# MSP430.net
KiCad netlist of a schematic drawn in Altium Designer
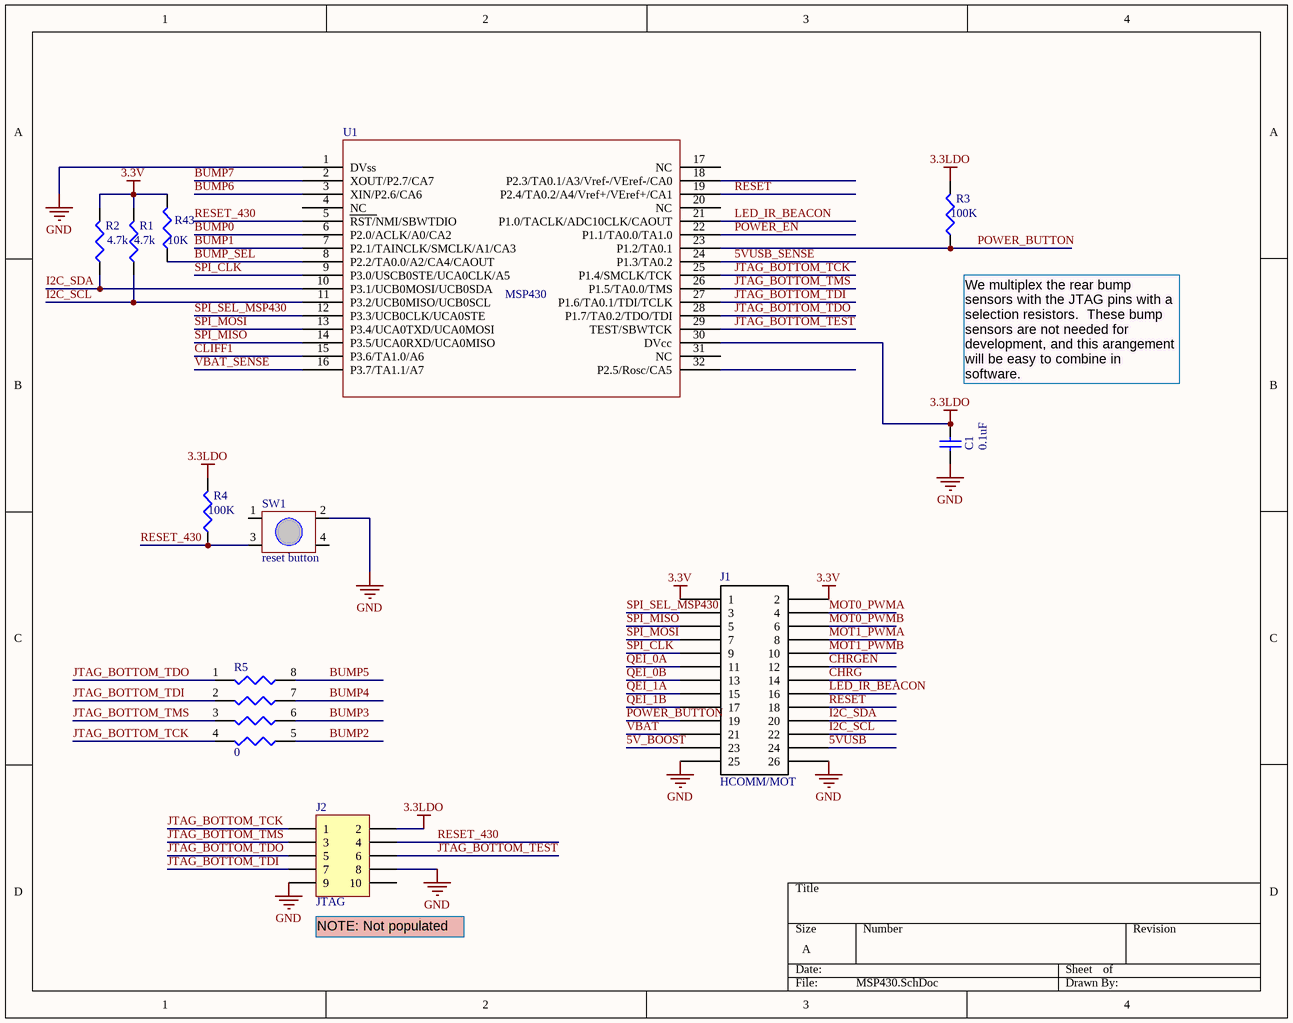
[diagram p0: MSP430.SchDoc]

(export (version "E")
  (design (tool "Eeschema 10.0.6"))
  (components
    (comp (ref "C1")
      (value "0.1uF")
      (footprint "CAPC1005L")
      (description "Capacitor (Semiconductor SIM Model)")
      (fields (field (name "Comment") "Cap Semi") (field (name "PUBLISHER") "Altium Limited"))
      (libsource (lib "Miscellaneous Devices") (part "Cap Semi"))
    )
    (comp (ref "J1")
      (value "HCOMM/MOT")
      (footprint "HeaderSM 13x2")
      (description "Header, 2X20, 50mil, IDC")
      (libsource (lib "mrone") (part "HCOMM/HMOT"))
    )
    (comp (ref "J2")
      (value "JTAG")
      (footprint "HDR2X5")
      (description "Header, 5-Pin, Dual row")
      (fields (field (name "PUBLISHER") "Altium Limited"))
      (libsource (lib "Miscellaneous Connectors") (part "Header 5X2"))
    )
    (comp (ref "R1")
      (value "4.7k")
      (footprint "RESC1608L")
      (description "Resistor")
      (fields (field (name "Comment") "Res3") (field (name "PUBLISHER") "Altium Limited"))
      (libsource (lib "Miscellaneous Devices") (part "Res3"))
    )
    (comp (ref "R2")
      (value "4.7k")
      (footprint "RESC1608L")
      (description "Resistor")
      (fields (field (name "Comment") "Res3") (field (name "PUBLISHER") "Altium Limited"))
      (libsource (lib "Miscellaneous Devices") (part "Res3"))
    )
    (comp (ref "R3")
      (value "100K")
      (footprint "RESC1608L")
      (description "Resistor")
      (fields (field (name "Comment") "Res3") (field (name "PUBLISHER") "Altium Limited"))
      (libsource (lib "Miscellaneous Devices") (part "Res3"))
    )
    (comp (ref "R4")
      (value "100K")
      (footprint "RESC1608L")
      (description "Resistor")
      (fields (field (name "Comment") "Res3") (field (name "PUBLISHER") "Altium Limited"))
      (libsource (lib "Miscellaneous Devices") (part "Res3"))
    )
    (comp (ref "R5") (value "0") (footprint "4-RES ARRAY") (libsource (lib "mrone") (part "4 Res Array")))
    (comp (ref "R43")
      (value "10K")
      (footprint "RESC1608L")
      (description "Resistor")
      (fields (field (name "Comment") "Res3") (field (name "PUBLISHER") "Altium Limited"))
      (libsource (lib "Miscellaneous Devices") (part "Res3"))
    )
    (comp (ref "SW1")
      (value "reset button")
      (footprint "SwitchTall-TL330")
      (libsource (lib "mrone") (part "Switch-TL330"))
    )
    (comp (ref "U1")
      (value "MSP430")
      (footprint "MSP430_32PIN")
      (libsource (lib "mrone") (part "MSP430_32pin"))
    )
  )
  (nets
    (net (code "1") (name "/5VUSB") (class "Default")
      (node (ref "J1") (pin "24") (pinfunction "24_24") (pintype "passive"))
    )
    (net (code "2") (name "/5VUSB_SENSE") (class "Default")
      (node (ref "U1") (pin "24") (pinfunction "P1.3/TA0.2_24") (pintype "passive"))
    )
    (net (code "3") (name "/5V_BOOST") (class "Default")
      (node (ref "J1") (pin "23") (pinfunction "23_23") (pintype "passive"))
    )
    (net (code "4") (name "/BUMP0") (class "Default")
      (node (ref "U1") (pin "6") (pinfunction "P2.0/ACLK/A0/CA2_6") (pintype "passive"))
    )
    (net (code "5") (name "/BUMP1") (class "Default")
      (node (ref "U1") (pin "7") (pinfunction "P2.1/TAINCLK/SMCLK/A1/CA3_7") (pintype "passive"))
    )
    (net (code "6") (name "/BUMP2") (class "Default")
      (node (ref "R5") (pin "5") (pinfunction "5_5") (pintype "passive"))
    )
    (net (code "7") (name "/BUMP3") (class "Default")
      (node (ref "R5") (pin "6") (pinfunction "6_6") (pintype "passive"))
    )
    (net (code "8") (name "/BUMP4") (class "Default")
      (node (ref "R5") (pin "7") (pinfunction "7_7") (pintype "passive"))
    )
    (net (code "9") (name "/BUMP5") (class "Default")
      (node (ref "R5") (pin "8") (pinfunction "8_8") (pintype "passive"))
    )
    (net (code "10") (name "/BUMP6") (class "Default")
      (node (ref "U1") (pin "3") (pinfunction "XIN/P2.6/CA6_3") (pintype "passive"))
    )
    (net (code "11") (name "/BUMP7") (class "Default")
      (node (ref "U1") (pin "2") (pinfunction "XOUT/P2.7/CA7_2") (pintype "passive"))
    )
    (net (code "12") (name "/BUMP_SEL") (class "Default")
      (node (ref "R43") (pin "1") (pinfunction "1_1") (pintype "passive"))
      (node (ref "U1") (pin "8") (pinfunction "P2.2/TA0.0/A2/CA4/CAOUT_8") (pintype "passive"))
    )
    (net (code "13") (name "/CHRG") (class "Default")
      (node (ref "J1") (pin "14") (pinfunction "14_14") (pintype "passive"))
    )
    (net (code "14") (name "/CHRGEN") (class "Default")
      (node (ref "J1") (pin "12") (pinfunction "12_12") (pintype "passive"))
    )
    (net (code "15") (name "/CLIFF1") (class "Default")
      (node (ref "U1") (pin "15") (pinfunction "P3.6/TA1.0/A6_15") (pintype "passive"))
    )
    (net (code "16") (name "/I2C_SCL") (class "Default")
      (node (ref "J1") (pin "22") (pinfunction "22_22") (pintype "passive"))
      (node (ref "R1") (pin "1") (pinfunction "1_1") (pintype "passive"))
      (node (ref "U1") (pin "11") (pinfunction "P3.2/UCB0MISO/UCB0SCL_11") (pintype "passive"))
    )
    (net (code "17") (name "/I2C_SDA") (class "Default")
      (node (ref "J1") (pin "20") (pinfunction "20_20") (pintype "passive"))
      (node (ref "R2") (pin "1") (pinfunction "1_1") (pintype "passive"))
      (node (ref "U1") (pin "10") (pinfunction "P3.1/UCB0MOSI/UCB0SDA_10") (pintype "passive"))
    )
    (net (code "18") (name "/JTAG_BOTTOM_TCK") (class "Default")
      (node (ref "J2") (pin "1") (pinfunction "1_1") (pintype "passive"))
      (node (ref "R5") (pin "4") (pinfunction "4_4") (pintype "passive"))
      (node (ref "U1") (pin "25") (pinfunction "P1.4/SMCLK/TCK_25") (pintype "passive"))
    )
    (net (code "19") (name "/JTAG_BOTTOM_TDI") (class "Default")
      (node (ref "J2") (pin "7") (pinfunction "7_7") (pintype "passive"))
      (node (ref "R5") (pin "2") (pinfunction "2_2") (pintype "passive"))
      (node (ref "U1") (pin "27") (pinfunction "P1.6/TA0.1/TDI/TCLK_27") (pintype "passive"))
    )
    (net (code "20") (name "/JTAG_BOTTOM_TDO") (class "Default")
      (node (ref "J2") (pin "5") (pinfunction "5_5") (pintype "passive"))
      (node (ref "R5") (pin "1") (pinfunction "1_1") (pintype "passive"))
      (node (ref "U1") (pin "28") (pinfunction "P1.7/TA0.2/TDO/TDI_28") (pintype "passive"))
    )
    (net (code "21") (name "/JTAG_BOTTOM_TEST") (class "Default")
      (node (ref "J2") (pin "6") (pinfunction "6_6") (pintype "passive"))
      (node (ref "U1") (pin "29") (pinfunction "TEST/SBWTCK_29") (pintype "passive"))
    )
    (net (code "22") (name "/JTAG_BOTTOM_TMS") (class "Default")
      (node (ref "J2") (pin "3") (pinfunction "3_3") (pintype "passive"))
      (node (ref "R5") (pin "3") (pinfunction "3_3") (pintype "passive"))
      (node (ref "U1") (pin "26") (pinfunction "P1.5/TA0.0/TMS_26") (pintype "passive"))
    )
    (net (code "23") (name "/LED_IR_BEACON") (class "Default")
      (node (ref "J1") (pin "16") (pinfunction "16_16") (pintype "passive"))
      (node (ref "U1") (pin "21") (pinfunction "P1.0/TACLK/ADC10CLK/CAOUT_21") (pintype "passive"))
    )
    (net (code "24") (name "/MOT0_PWMA") (class "Default")
      (node (ref "J1") (pin "4") (pinfunction "4_4") (pintype "passive"))
    )
    (net (code "25") (name "/MOT0_PWMB") (class "Default")
      (node (ref "J1") (pin "6") (pinfunction "6_6") (pintype "passive"))
    )
    (net (code "26") (name "/MOT1_PWMA") (class "Default")
      (node (ref "J1") (pin "8") (pinfunction "8_8") (pintype "passive"))
    )
    (net (code "27") (name "/MOT1_PWMB") (class "Default")
      (node (ref "J1") (pin "10") (pinfunction "10_10") (pintype "passive"))
    )
    (net (code "28") (name "/POWER_BUTTON") (class "Default")
      (node (ref "J1") (pin "19") (pinfunction "19_19") (pintype "passive"))
      (node (ref "R3") (pin "1") (pinfunction "1_1") (pintype "passive"))
      (node (ref "U1") (pin "23") (pinfunction "P1.2/TA0.1_23") (pintype "passive"))
    )
    (net (code "29") (name "/POWER_EN") (class "Default")
      (node (ref "U1") (pin "22") (pinfunction "P1.1/TA0.0/TA1.0_22") (pintype "passive"))
    )
    (net (code "30") (name "/QEI_0A") (class "Default")
      (node (ref "J1") (pin "11") (pinfunction "11_11") (pintype "passive"))
    )
    (net (code "31") (name "/QEI_0B") (class "Default")
      (node (ref "J1") (pin "13") (pinfunction "13_13") (pintype "passive"))
    )
    (net (code "32") (name "/QEI_1A") (class "Default")
      (node (ref "J1") (pin "15") (pinfunction "15_15") (pintype "passive"))
    )
    (net (code "33") (name "/QEI_1B") (class "Default")
      (node (ref "J1") (pin "17") (pinfunction "17_17") (pintype "passive"))
    )
    (net (code "34") (name "/RESET") (class "Default")
      (node (ref "J1") (pin "18") (pinfunction "18_18") (pintype "passive"))
      (node (ref "U1") (pin "19") (pinfunction "P2.4/TA0.2/A4/Vref+/VEref+/CA1_19") (pintype "passive"))
    )
    (net (code "35") (name "/RESET_430") (class "Default")
      (node (ref "J2") (pin "4") (pinfunction "4_4") (pintype "passive"))
      (node (ref "R4") (pin "1") (pinfunction "1_1") (pintype "passive"))
      (node (ref "SW1") (pin "3") (pinfunction "3_3") (pintype "passive"))
      (node (ref "U1") (pin "5") (pinfunction "RST/NMI/SBWTDIO_5") (pintype "passive"))
    )
    (net (code "36") (name "/SPI_CLK") (class "Default")
      (node (ref "J1") (pin "9") (pinfunction "9_9") (pintype "passive"))
      (node (ref "U1") (pin "9") (pinfunction "P3.0/USCB0STE/UCA0CLK/A5_9") (pintype "passive"))
    )
    (net (code "37") (name "/SPI_MISO") (class "Default")
      (node (ref "J1") (pin "5") (pinfunction "5_5") (pintype "passive"))
      (node (ref "U1") (pin "14") (pinfunction "P3.5/UCA0RXD/UCA0MISO_14") (pintype "passive"))
    )
    (net (code "38") (name "/SPI_MOSI") (class "Default")
      (node (ref "J1") (pin "7") (pinfunction "7_7") (pintype "passive"))
      (node (ref "U1") (pin "13") (pinfunction "P3.4/UCA0TXD/UCA0MOSI_13") (pintype "passive"))
    )
    (net (code "39") (name "/SPI_SEL_MSP430") (class "Default")
      (node (ref "J1") (pin "3") (pinfunction "3_3") (pintype "passive"))
      (node (ref "U1") (pin "12") (pinfunction "P3.3/UCB0CLK/UCA0STE_12") (pintype "passive"))
    )
    (net (code "40") (name "/VBAT") (class "Default")
      (node (ref "J1") (pin "21") (pinfunction "21_21") (pintype "passive"))
    )
    (net (code "41") (name "/VBAT_SENSE") (class "Default")
      (node (ref "U1") (pin "16") (pinfunction "P3.7/TA1.1/A7_16") (pintype "passive"))
    )
    (net (code "42") (name "3.3LDO") (class "Default")
      (node (ref "C1") (pin "2") (pinfunction "2_2") (pintype "passive"))
      (node (ref "J2") (pin "2") (pinfunction "2_2") (pintype "passive"))
      (node (ref "R3") (pin "2") (pinfunction "2_2") (pintype "passive"))
      (node (ref "R4") (pin "2") (pinfunction "2_2") (pintype "passive"))
      (node (ref "U1") (pin "30") (pinfunction "DVcc_30") (pintype "passive"))
    )
    (net (code "43") (name "3.3V") (class "Default")
      (node (ref "J1") (pin "1") (pinfunction "1_1") (pintype "passive"))
      (node (ref "J1") (pin "2") (pinfunction "2_2") (pintype "passive"))
      (node (ref "R1") (pin "2") (pinfunction "2_2") (pintype "passive"))
      (node (ref "R2") (pin "2") (pinfunction "2_2") (pintype "passive"))
      (node (ref "R43") (pin "2") (pinfunction "2_2") (pintype "passive"))
    )
    (net (code "44") (name "GND") (class "Default")
      (node (ref "C1") (pin "1") (pinfunction "1_1") (pintype "passive"))
      (node (ref "J1") (pin "25") (pinfunction "25_25") (pintype "passive"))
      (node (ref "J1") (pin "26") (pinfunction "26_26") (pintype "passive"))
      (node (ref "J2") (pin "8") (pinfunction "8_8") (pintype "passive"))
      (node (ref "J2") (pin "9") (pinfunction "9_9") (pintype "passive"))
      (node (ref "SW1") (pin "2") (pinfunction "2_2") (pintype "passive"))
      (node (ref "U1") (pin "1") (pinfunction "DVss_1") (pintype "passive"))
    )
    (net (code "45") (name "unconnected-(J2-Pad10)") (class "Default")
      (node (ref "J2") (pin "10") (pinfunction "10_10") (pintype "passive"))
    )
    (net (code "46") (name "unconnected-(R5-Pad1)") (class "Default")
      (node (ref "R5") (pin "1") (pinfunction "1_1") (pintype "passive"))
    )
    (net (code "47") (name "unconnected-(R5-Pad1)_1") (class "Default")
      (node (ref "R5") (pin "1") (pinfunction "1_1") (pintype "passive"))
    )
    (net (code "48") (name "unconnected-(R5-Pad1)_2") (class "Default")
      (node (ref "R5") (pin "1") (pinfunction "1_1") (pintype "passive"))
    )
    (net (code "49") (name "unconnected-(R5-Pad1)_3") (class "Default")
      (node (ref "R5") (pin "1") (pinfunction "1_1") (pintype "passive"))
    )
    (net (code "50") (name "unconnected-(R5-Pad2)") (class "Default")
      (node (ref "R5") (pin "2") (pinfunction "2_2") (pintype "passive"))
    )
    (net (code "51") (name "unconnected-(R5-Pad2)_1") (class "Default")
      (node (ref "R5") (pin "2") (pinfunction "2_2") (pintype "passive"))
    )
    (net (code "52") (name "unconnected-(R5-Pad2)_2") (class "Default")
      (node (ref "R5") (pin "2") (pinfunction "2_2") (pintype "passive"))
    )
    (net (code "53") (name "unconnected-(R5-Pad2)_3") (class "Default")
      (node (ref "R5") (pin "2") (pinfunction "2_2") (pintype "passive"))
    )
    (net (code "54") (name "unconnected-(SW1-Pad1)") (class "Default")
      (node (ref "SW1") (pin "1") (pinfunction "1_1") (pintype "passive"))
    )
    (net (code "55") (name "unconnected-(SW1-Pad4)") (class "Default")
      (node (ref "SW1") (pin "4") (pinfunction "4_4") (pintype "passive"))
    )
    (net (code "56") (name "unconnected-(U1-NC-Pad4)") (class "Default")
      (node (ref "U1") (pin "4") (pinfunction "NC_4") (pintype "passive"))
    )
    (net (code "57") (name "unconnected-(U1-NC-Pad17)") (class "Default")
      (node (ref "U1") (pin "17") (pinfunction "NC_17") (pintype "passive"))
    )
    (net (code "58") (name "unconnected-(U1-NC-Pad20)") (class "Default")
      (node (ref "U1") (pin "20") (pinfunction "NC_20") (pintype "passive"))
    )
    (net (code "59") (name "unconnected-(U1-NC-Pad31)") (class "Default")
      (node (ref "U1") (pin "31") (pinfunction "NC_31") (pintype "passive"))
    )
    (net (code "60") (name "unconnected-(U1-P2.3{slash}TA0.1{slash}A3{slash}Vref-{slash}VEref-{slash}CA0-Pad18)") (class "Default")
      (node (ref "U1") (pin "18") (pinfunction "P2.3/TA0.1/A3/Vref-/VEref-/CA0_18") (pintype "passive"))
    )
    (net (code "61") (name "unconnected-(U1-P2.5{slash}Rosc{slash}CA5-Pad32)") (class "Default")
      (node (ref "U1") (pin "32") (pinfunction "P2.5/Rosc/CA5_32") (pintype "passive"))
    )
  )
)
